# PLBank33.net
KiCad netlist of a schematic drawn in Altium Designer
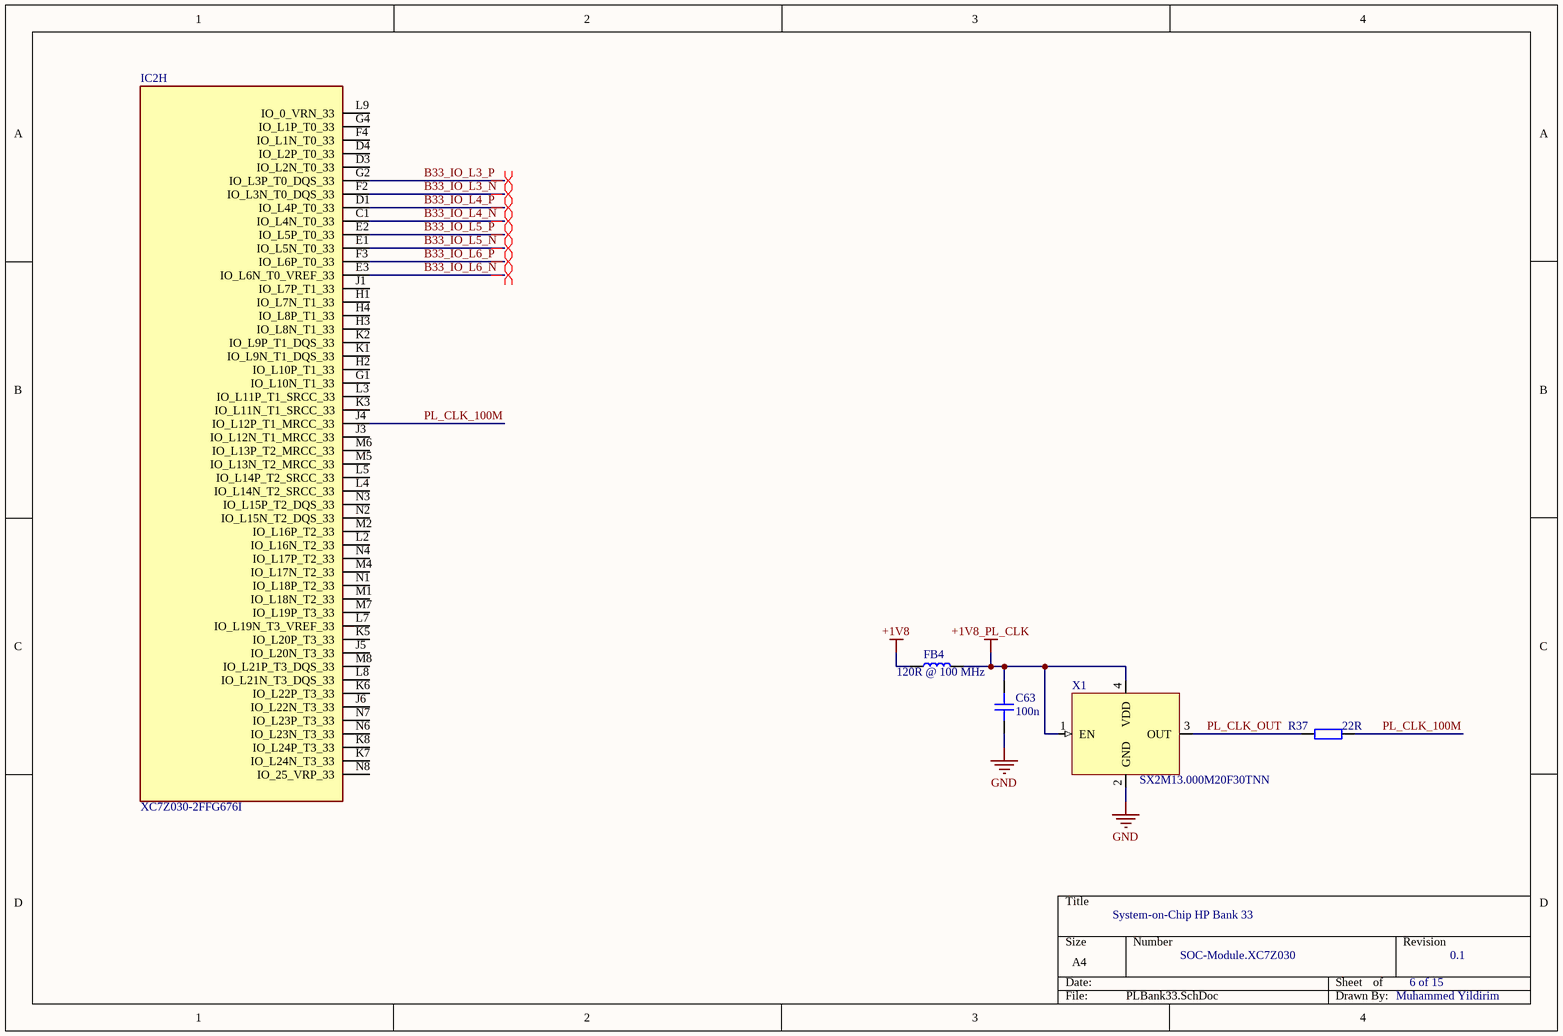
[diagram p0: PLBank33.SchDoc]

(export (version "E")
  (design (tool "Eeschema 10.0.6"))
  (components
    (comp (ref "C63")
      (value "100n")
      (footprint "CAP_0201")
      (description "Capacitor SMD 0201")
      (libsource (lib "Schematic-Lib-PhilsLab") (part "CAP_0201"))
    )
    (comp (ref "FB4")
      (value "120R @ 100 MHz")
      (footprint "Footprint-Lib-PhilsLab:IND_0201")
      (description "Inductor SMD 0201")
      (fields
        (field (name "MANUFACTURER_PART_NUMBER") "LQP03HQ56NH02D")
        (field (name "MOUSER PART NUMBER") "81-LQP03HQ56NH02D")
      )
      (libsource (lib "Schematic-Lib-PhilsLab") (part "IND_0201"))
    )
    (comp (ref "IC2")
      (value "XC7Z030-2FFG676I")
      (footprint "XC7Z030PCBLib:BGA676C100P26X26_2700X2700X324")
      (description "Integrated Circuit")
      (fields (field (name "MOUSER PART NUMBER") "217-XC7Z030-2FFG676I"))
      (libsource (lib "XC7Z030SCHLib") (part "XC7Z030-2FFG676I"))
    )
    (comp (ref "R37")
      (value "22R")
      (footprint "RES_0201")
      (description "Resistor SMD 0201")
      (libsource (lib "Schematic-Lib-PhilsLab") (part "RES_0201"))
    )
    (comp (ref "X1")
      (value "SX2M13.000M20F30TNN")
      (footprint "XTAL_2520")
      (fields
        (field (name "MANUFACTURER") "ECS")
        (field (name "MANUFACTURER PART NUMBER") "ECS-2520MV-130-BN-TR")
      )
      (libsource (lib "Schematic-Lib-PhilsLab") (part "ECS-2520MV-130-BN-TR"))
    )
  )
  (nets
    (net (code "1") (name "+1V8") (class "Default")
      (node (ref "FB4") (pin "1") (pinfunction "1_1") (pintype "passive"))
    )
    (net (code "2") (name "+1V8_PL_CLK") (class "Default")
      (node (ref "C63") (pin "1") (pinfunction "1_1") (pintype "passive"))
      (node (ref "FB4") (pin "2") (pinfunction "2_2") (pintype "passive"))
      (node (ref "X1") (pin "1") (pinfunction "EN_1") (pintype "input"))
      (node (ref "X1") (pin "4") (pinfunction "VDD_4") (pintype "power_in"))
    )
    (net (code "3") (name "/B33_IO_L3_N") (class "Default")
      (node (ref "IC2") (pin "F2") (pinfunction "IO_L3N_T0_DQS_33_F2") (pintype "passive"))
    )
    (net (code "4") (name "/B33_IO_L3_P") (class "Default")
      (node (ref "IC2") (pin "G2") (pinfunction "IO_L3P_T0_DQS_33_G2") (pintype "passive"))
    )
    (net (code "5") (name "/B33_IO_L4_N") (class "Default")
      (node (ref "IC2") (pin "C1") (pinfunction "IO_L4N_T0_33_C1") (pintype "passive"))
    )
    (net (code "6") (name "/B33_IO_L4_P") (class "Default")
      (node (ref "IC2") (pin "D1") (pinfunction "IO_L4P_T0_33_D1") (pintype "passive"))
    )
    (net (code "7") (name "/B33_IO_L5_N") (class "Default")
      (node (ref "IC2") (pin "E1") (pinfunction "IO_L5N_T0_33_E1") (pintype "passive"))
    )
    (net (code "8") (name "/B33_IO_L5_P") (class "Default")
      (node (ref "IC2") (pin "E2") (pinfunction "IO_L5P_T0_33_E2") (pintype "passive"))
    )
    (net (code "9") (name "/B33_IO_L6_N") (class "Default")
      (node (ref "IC2") (pin "E3") (pinfunction "IO_L6N_T0_VREF_33_E3") (pintype "passive"))
    )
    (net (code "10") (name "/B33_IO_L6_P") (class "Default")
      (node (ref "IC2") (pin "F3") (pinfunction "IO_L6P_T0_33_F3") (pintype "passive"))
    )
    (net (code "11") (name "/PL_CLK_100M") (class "Default")
      (node (ref "IC2") (pin "J4") (pinfunction "IO_L12P_T1_MRCC_33_J4") (pintype "passive"))
      (node (ref "R37") (pin "2") (pinfunction "2_2") (pintype "passive"))
    )
    (net (code "12") (name "/PL_CLK_OUT") (class "Default")
      (node (ref "R37") (pin "1") (pinfunction "1_1") (pintype "passive"))
      (node (ref "X1") (pin "3") (pinfunction "OUT_3") (pintype "passive"))
    )
    (net (code "13") (name "GND") (class "Default")
      (node (ref "C63") (pin "2") (pinfunction "2_2") (pintype "passive"))
      (node (ref "X1") (pin "2") (pinfunction "GND_2") (pintype "power_in"))
    )
    (net (code "14") (name "unconnected-(IC2H-IO_0_VRN_33-PadL9)") (class "Default")
      (node (ref "IC2") (pin "L9") (pinfunction "IO_0_VRN_33_L9") (pintype "passive"))
    )
    (net (code "15") (name "unconnected-(IC2H-IO_25_VRP_33-PadN8)") (class "Default")
      (node (ref "IC2") (pin "N8") (pinfunction "IO_25_VRP_33_N8") (pintype "passive"))
    )
    (net (code "16") (name "unconnected-(IC2H-IO_L1N_T0_33-PadF4)") (class "Default")
      (node (ref "IC2") (pin "F4") (pinfunction "IO_L1N_T0_33_F4") (pintype "passive"))
    )
    (net (code "17") (name "unconnected-(IC2H-IO_L1P_T0_33-PadG4)") (class "Default")
      (node (ref "IC2") (pin "G4") (pinfunction "IO_L1P_T0_33_G4") (pintype "passive"))
    )
    (net (code "18") (name "unconnected-(IC2H-IO_L2N_T0_33-PadD3)") (class "Default")
      (node (ref "IC2") (pin "D3") (pinfunction "IO_L2N_T0_33_D3") (pintype "passive"))
    )
    (net (code "19") (name "unconnected-(IC2H-IO_L2P_T0_33-PadD4)") (class "Default")
      (node (ref "IC2") (pin "D4") (pinfunction "IO_L2P_T0_33_D4") (pintype "passive"))
    )
    (net (code "20") (name "unconnected-(IC2H-IO_L7N_T1_33-PadH1)") (class "Default")
      (node (ref "IC2") (pin "H1") (pinfunction "IO_L7N_T1_33_H1") (pintype "passive"))
    )
    (net (code "21") (name "unconnected-(IC2H-IO_L7P_T1_33-PadJ1)") (class "Default")
      (node (ref "IC2") (pin "J1") (pinfunction "IO_L7P_T1_33_J1") (pintype "passive"))
    )
    (net (code "22") (name "unconnected-(IC2H-IO_L8N_T1_33-PadH3)") (class "Default")
      (node (ref "IC2") (pin "H3") (pinfunction "IO_L8N_T1_33_H3") (pintype "passive"))
    )
    (net (code "23") (name "unconnected-(IC2H-IO_L8P_T1_33-PadH4)") (class "Default")
      (node (ref "IC2") (pin "H4") (pinfunction "IO_L8P_T1_33_H4") (pintype "passive"))
    )
    (net (code "24") (name "unconnected-(IC2H-IO_L9N_T1_DQS_33-PadK1)") (class "Default")
      (node (ref "IC2") (pin "K1") (pinfunction "IO_L9N_T1_DQS_33_K1") (pintype "passive"))
    )
    (net (code "25") (name "unconnected-(IC2H-IO_L9P_T1_DQS_33-PadK2)") (class "Default")
      (node (ref "IC2") (pin "K2") (pinfunction "IO_L9P_T1_DQS_33_K2") (pintype "passive"))
    )
    (net (code "26") (name "unconnected-(IC2H-IO_L10N_T1_33-PadG1)") (class "Default")
      (node (ref "IC2") (pin "G1") (pinfunction "IO_L10N_T1_33_G1") (pintype "passive"))
    )
    (net (code "27") (name "unconnected-(IC2H-IO_L10P_T1_33-PadH2)") (class "Default")
      (node (ref "IC2") (pin "H2") (pinfunction "IO_L10P_T1_33_H2") (pintype "passive"))
    )
    (net (code "28") (name "unconnected-(IC2H-IO_L11N_T1_SRCC_33-PadK3)") (class "Default")
      (node (ref "IC2") (pin "K3") (pinfunction "IO_L11N_T1_SRCC_33_K3") (pintype "passive"))
    )
    (net (code "29") (name "unconnected-(IC2H-IO_L11P_T1_SRCC_33-PadL3)") (class "Default")
      (node (ref "IC2") (pin "L3") (pinfunction "IO_L11P_T1_SRCC_33_L3") (pintype "passive"))
    )
    (net (code "30") (name "unconnected-(IC2H-IO_L12N_T1_MRCC_33-PadJ3)") (class "Default")
      (node (ref "IC2") (pin "J3") (pinfunction "IO_L12N_T1_MRCC_33_J3") (pintype "passive"))
    )
    (net (code "31") (name "unconnected-(IC2H-IO_L13N_T2_MRCC_33-PadM5)") (class "Default")
      (node (ref "IC2") (pin "M5") (pinfunction "IO_L13N_T2_MRCC_33_M5") (pintype "passive"))
    )
    (net (code "32") (name "unconnected-(IC2H-IO_L13P_T2_MRCC_33-PadM6)") (class "Default")
      (node (ref "IC2") (pin "M6") (pinfunction "IO_L13P_T2_MRCC_33_M6") (pintype "passive"))
    )
    (net (code "33") (name "unconnected-(IC2H-IO_L14N_T2_SRCC_33-PadL4)") (class "Default")
      (node (ref "IC2") (pin "L4") (pinfunction "IO_L14N_T2_SRCC_33_L4") (pintype "passive"))
    )
    (net (code "34") (name "unconnected-(IC2H-IO_L14P_T2_SRCC_33-PadL5)") (class "Default")
      (node (ref "IC2") (pin "L5") (pinfunction "IO_L14P_T2_SRCC_33_L5") (pintype "passive"))
    )
    (net (code "35") (name "unconnected-(IC2H-IO_L15N_T2_DQS_33-PadN2)") (class "Default")
      (node (ref "IC2") (pin "N2") (pinfunction "IO_L15N_T2_DQS_33_N2") (pintype "passive"))
    )
    (net (code "36") (name "unconnected-(IC2H-IO_L15P_T2_DQS_33-PadN3)") (class "Default")
      (node (ref "IC2") (pin "N3") (pinfunction "IO_L15P_T2_DQS_33_N3") (pintype "passive"))
    )
    (net (code "37") (name "unconnected-(IC2H-IO_L16N_T2_33-PadL2)") (class "Default")
      (node (ref "IC2") (pin "L2") (pinfunction "IO_L16N_T2_33_L2") (pintype "passive"))
    )
    (net (code "38") (name "unconnected-(IC2H-IO_L16P_T2_33-PadM2)") (class "Default")
      (node (ref "IC2") (pin "M2") (pinfunction "IO_L16P_T2_33_M2") (pintype "passive"))
    )
    (net (code "39") (name "unconnected-(IC2H-IO_L17N_T2_33-PadM4)") (class "Default")
      (node (ref "IC2") (pin "M4") (pinfunction "IO_L17N_T2_33_M4") (pintype "passive"))
    )
    (net (code "40") (name "unconnected-(IC2H-IO_L17P_T2_33-PadN4)") (class "Default")
      (node (ref "IC2") (pin "N4") (pinfunction "IO_L17P_T2_33_N4") (pintype "passive"))
    )
    (net (code "41") (name "unconnected-(IC2H-IO_L18N_T2_33-PadM1)") (class "Default")
      (node (ref "IC2") (pin "M1") (pinfunction "IO_L18N_T2_33_M1") (pintype "passive"))
    )
    (net (code "42") (name "unconnected-(IC2H-IO_L18P_T2_33-PadN1)") (class "Default")
      (node (ref "IC2") (pin "N1") (pinfunction "IO_L18P_T2_33_N1") (pintype "passive"))
    )
    (net (code "43") (name "unconnected-(IC2H-IO_L19N_T3_VREF_33-PadL7)") (class "Default")
      (node (ref "IC2") (pin "L7") (pinfunction "IO_L19N_T3_VREF_33_L7") (pintype "passive"))
    )
    (net (code "44") (name "unconnected-(IC2H-IO_L19P_T3_33-PadM7)") (class "Default")
      (node (ref "IC2") (pin "M7") (pinfunction "IO_L19P_T3_33_M7") (pintype "passive"))
    )
    (net (code "45") (name "unconnected-(IC2H-IO_L20N_T3_33-PadJ5)") (class "Default")
      (node (ref "IC2") (pin "J5") (pinfunction "IO_L20N_T3_33_J5") (pintype "passive"))
    )
    (net (code "46") (name "unconnected-(IC2H-IO_L20P_T3_33-PadK5)") (class "Default")
      (node (ref "IC2") (pin "K5") (pinfunction "IO_L20P_T3_33_K5") (pintype "passive"))
    )
    (net (code "47") (name "unconnected-(IC2H-IO_L21N_T3_DQS_33-PadL8)") (class "Default")
      (node (ref "IC2") (pin "L8") (pinfunction "IO_L21N_T3_DQS_33_L8") (pintype "passive"))
    )
    (net (code "48") (name "unconnected-(IC2H-IO_L21P_T3_DQS_33-PadM8)") (class "Default")
      (node (ref "IC2") (pin "M8") (pinfunction "IO_L21P_T3_DQS_33_M8") (pintype "passive"))
    )
    (net (code "49") (name "unconnected-(IC2H-IO_L22N_T3_33-PadJ6)") (class "Default")
      (node (ref "IC2") (pin "J6") (pinfunction "IO_L22N_T3_33_J6") (pintype "passive"))
    )
    (net (code "50") (name "unconnected-(IC2H-IO_L22P_T3_33-PadK6)") (class "Default")
      (node (ref "IC2") (pin "K6") (pinfunction "IO_L22P_T3_33_K6") (pintype "passive"))
    )
    (net (code "51") (name "unconnected-(IC2H-IO_L23N_T3_33-PadN6)") (class "Default")
      (node (ref "IC2") (pin "N6") (pinfunction "IO_L23N_T3_33_N6") (pintype "passive"))
    )
    (net (code "52") (name "unconnected-(IC2H-IO_L23P_T3_33-PadN7)") (class "Default")
      (node (ref "IC2") (pin "N7") (pinfunction "IO_L23P_T3_33_N7") (pintype "passive"))
    )
    (net (code "53") (name "unconnected-(IC2H-IO_L24N_T3_33-PadK7)") (class "Default")
      (node (ref "IC2") (pin "K7") (pinfunction "IO_L24N_T3_33_K7") (pintype "passive"))
    )
    (net (code "54") (name "unconnected-(IC2H-IO_L24P_T3_33-PadK8)") (class "Default")
      (node (ref "IC2") (pin "K8") (pinfunction "IO_L24P_T3_33_K8") (pintype "passive"))
    )
  )
)
